# stm32f103cb_lcd32.net
KiCad netlist of a schematic drawn in EAGLE
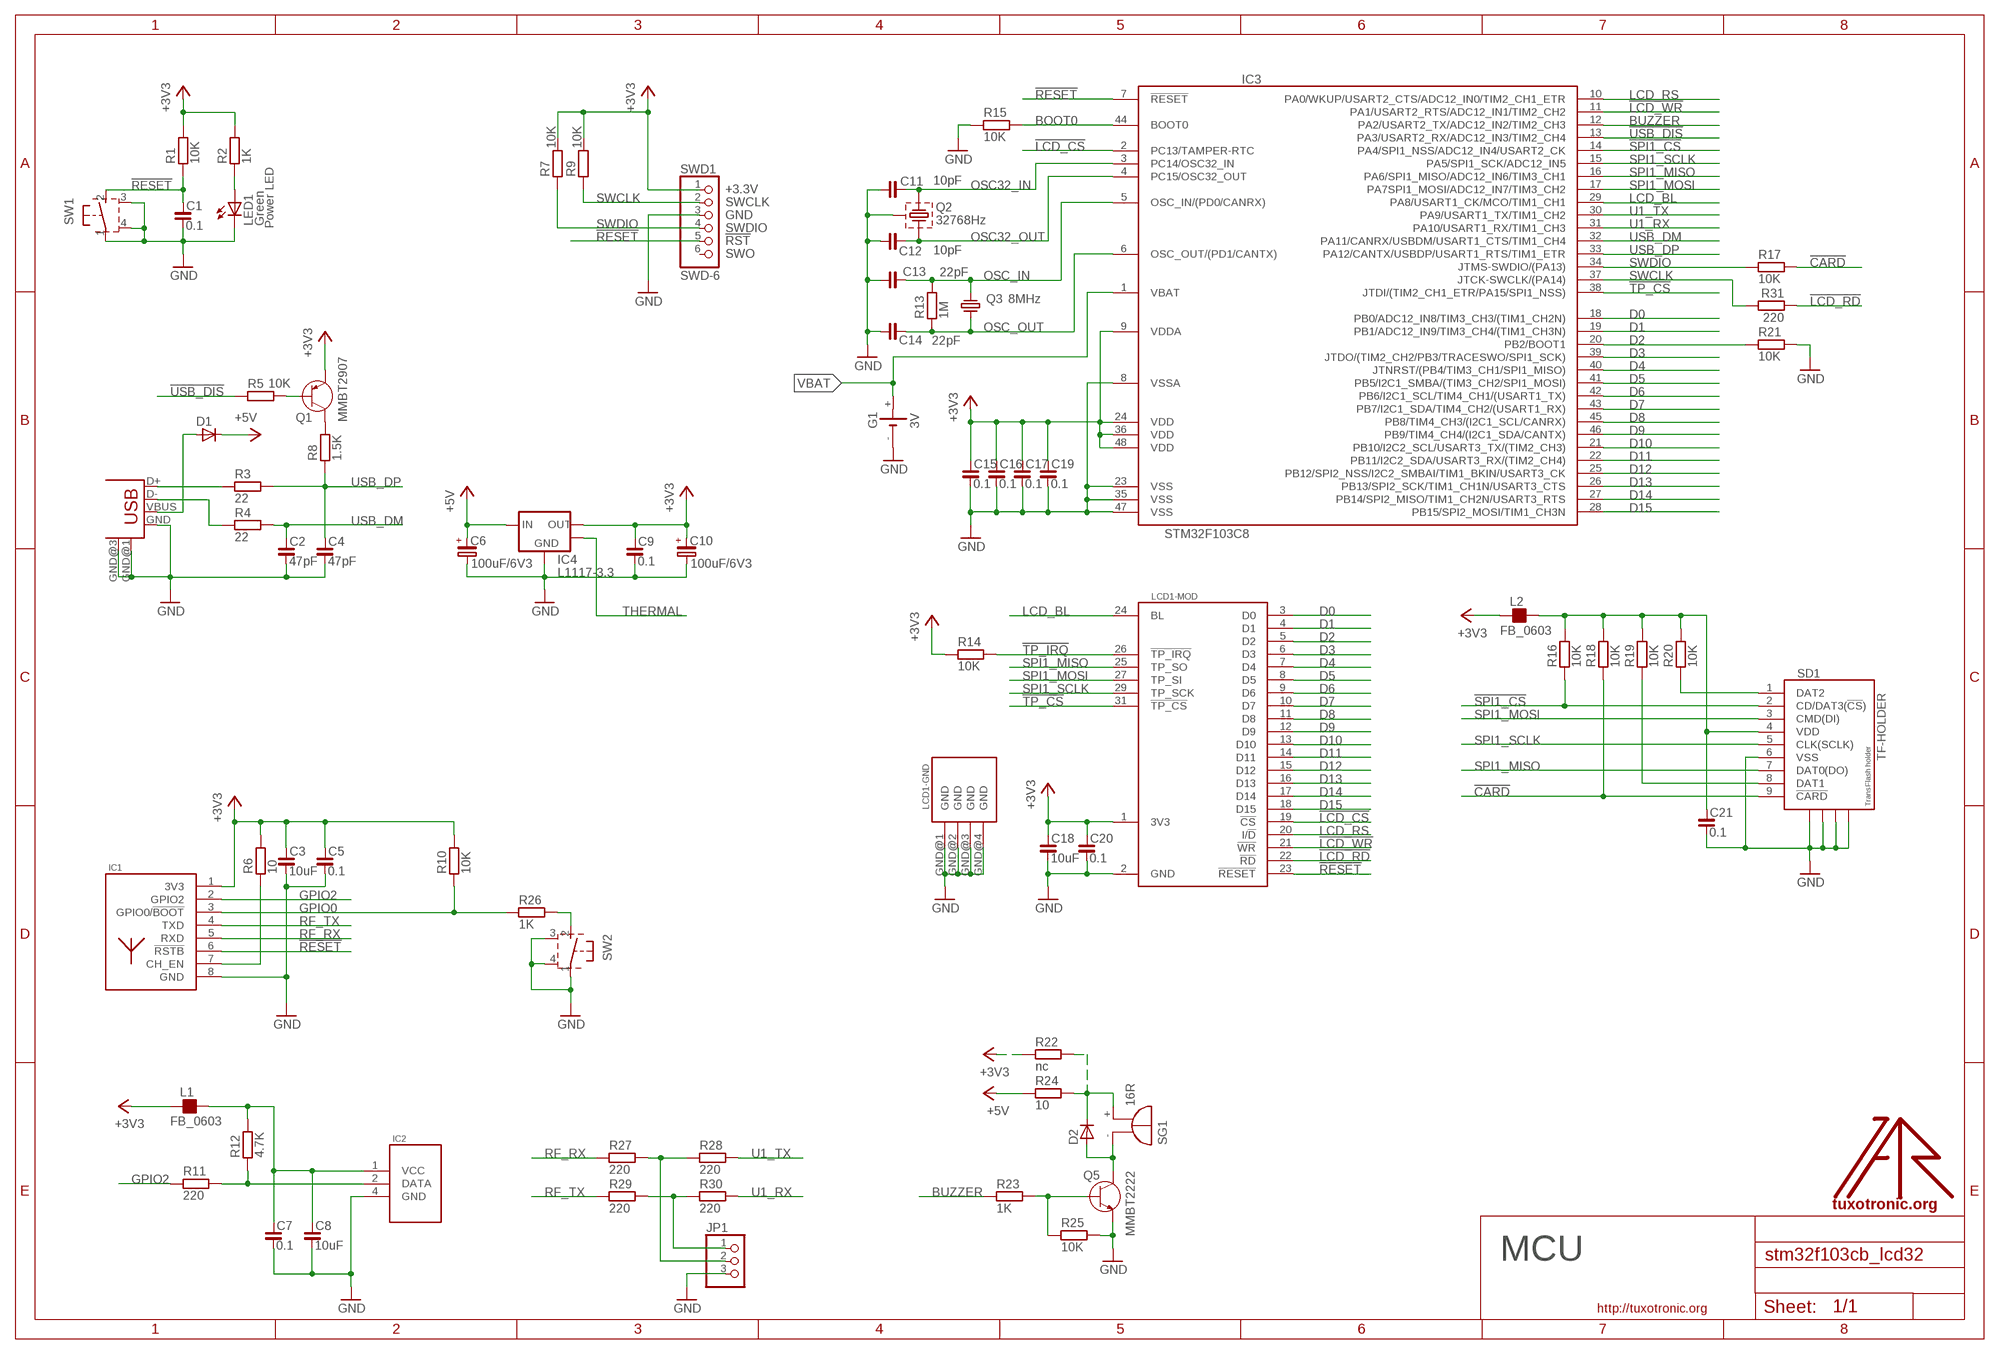
[diagram p0: schematic, sheet 1]

(export (version "E")
  (design (tool "Eeschema 10.0.6"))
  (components
    (comp (ref "C1")
      (value "0.1")
      (footprint "eagle-import:C0603")
      (libsource (lib "eagle-import") (part "C_0603"))
    )
    (comp (ref "C2")
      (value "47pF")
      (footprint "eagle-import:C0603")
      (libsource (lib "eagle-import") (part "C_0603"))
    )
    (comp (ref "C3")
      (value "10uF")
      (footprint "eagle-import:C0805")
      (libsource (lib "eagle-import") (part "C_0805"))
    )
    (comp (ref "C4")
      (value "47pF")
      (footprint "eagle-import:C0603")
      (libsource (lib "eagle-import") (part "C_0603"))
    )
    (comp (ref "C5")
      (value "0.1")
      (footprint "eagle-import:C0603")
      (libsource (lib "eagle-import") (part "C_0603"))
    )
    (comp (ref "C6")
      (value "100uF/6V3")
      (footprint "eagle-import:SMC_D")
      (libsource (lib "eagle-import") (part "CP_SMCD"))
    )
    (comp (ref "C7")
      (value "0.1")
      (footprint "eagle-import:C0603")
      (libsource (lib "eagle-import") (part "C_0603"))
    )
    (comp (ref "C8")
      (value "10uF")
      (footprint "eagle-import:C0805")
      (libsource (lib "eagle-import") (part "C_0805"))
    )
    (comp (ref "C9")
      (value "0.1")
      (footprint "eagle-import:C0805")
      (libsource (lib "eagle-import") (part "C_0805"))
    )
    (comp (ref "C10")
      (value "100uF/6V3")
      (footprint "eagle-import:SMC_D")
      (libsource (lib "eagle-import") (part "CP_SMCD"))
    )
    (comp (ref "C11")
      (value "10pF")
      (footprint "eagle-import:C0603")
      (libsource (lib "eagle-import") (part "C_0603"))
    )
    (comp (ref "C12")
      (value "10pF")
      (footprint "eagle-import:C0603")
      (libsource (lib "eagle-import") (part "C_0603"))
    )
    (comp (ref "C13")
      (value "22pF")
      (footprint "eagle-import:C0603")
      (libsource (lib "eagle-import") (part "C_0603"))
    )
    (comp (ref "C14")
      (value "22pF")
      (footprint "eagle-import:C0603")
      (libsource (lib "eagle-import") (part "C_0603"))
    )
    (comp (ref "C15")
      (value "0.1")
      (footprint "eagle-import:C0603")
      (libsource (lib "eagle-import") (part "C_0603"))
    )
    (comp (ref "C16")
      (value "0.1")
      (footprint "eagle-import:C0603")
      (libsource (lib "eagle-import") (part "C_0603"))
    )
    (comp (ref "C17")
      (value "0.1")
      (footprint "eagle-import:C0603")
      (libsource (lib "eagle-import") (part "C_0603"))
    )
    (comp (ref "C18")
      (value "10uF")
      (footprint "eagle-import:C0805")
      (libsource (lib "eagle-import") (part "C_0805"))
    )
    (comp (ref "C19")
      (value "0.1")
      (footprint "eagle-import:C0603")
      (libsource (lib "eagle-import") (part "C_0603"))
    )
    (comp (ref "C20")
      (value "0.1")
      (footprint "eagle-import:C0603")
      (libsource (lib "eagle-import") (part "C_0603"))
    )
    (comp (ref "C21")
      (value "0.1")
      (footprint "eagle-import:C0603")
      (libsource (lib "eagle-import") (part "C_0603"))
    )
    (comp (ref "D1")
      (value "D-SMB")
      (footprint "eagle-import:SMB")
      (libsource (lib "eagle-import") (part "D-SMB"))
    )
    (comp (ref "D2")
      (value "D-SOD-80")
      (footprint "eagle-import:SOD80")
      (libsource (lib "eagle-import") (part "D-SOD-80"))
    )
    (comp (ref "G1")
      (value "3V")
      (footprint "eagle-import:SMT1220")
      (libsource (lib "eagle-import") (part "1220SMT"))
    )
    (comp (ref "IC1")
      (value "ESP-11")
      (footprint "eagle-import:ESP11")
      (libsource (lib "eagle-import") (part "ESP-11"))
    )
    (comp (ref "IC2")
      (value "DHT22")
      (footprint "eagle-import:DHT")
      (libsource (lib "eagle-import") (part "DHT22"))
    )
    (comp (ref "IC3")
      (value "STM32F103C8")
      (footprint "eagle-import:LQFP48")
      (libsource (lib "eagle-import") (part "STM32F103C8"))
    )
    (comp (ref "IC4")
      (value "L1117-3.3")
      (footprint "eagle-import:SOT223-THP")
      (libsource (lib "eagle-import") (part "LM1117-THP"))
    )
    (comp (ref "JP1")
      (value "PINHD-1X3_2.54S")
      (footprint "eagle-import:1X03SMALL")
      (libsource (lib "eagle-import") (part "PINHD-1X3_2.54S"))
    )
    (comp (ref "L1")
      (value "FB_0603")
      (footprint "eagle-import:L0603")
      (libsource (lib "eagle-import") (part "FB_0603"))
    )
    (comp (ref "L2")
      (value "FB_0603")
      (footprint "eagle-import:L0603")
      (libsource (lib "eagle-import") (part "FB_0603"))
    )
    (comp (ref "LCD1")
      (value "YX32B")
      (footprint "eagle-import:YX32B")
      (libsource (lib "eagle-import") (part "YX32B"))
    )
    (comp (ref "LED1")
      (value "Green")
      (footprint "eagle-import:CHIP-LED0805")
      (libsource (lib "eagle-import") (part "LEDCHIP-LED0805"))
    )
    (comp (ref "LOGO1")
      (value "LOGO")
      (footprint "eagle-import:TT_LOGO")
      (libsource (lib "eagle-import") (part "LOGO"))
    )
    (comp (ref "Q1")
      (value "MMBT2907")
      (footprint "eagle-import:SOT23")
      (libsource (lib "eagle-import") (part "PNP-SOT23"))
    )
    (comp (ref "Q2")
      (value "32768Hz")
      (footprint "eagle-import:TC38H-G")
      (libsource (lib "eagle-import") (part "CRSTL3-"))
    )
    (comp (ref "Q3")
      (value "8MHz")
      (footprint "eagle-import:HC49_S")
      (libsource (lib "eagle-import") (part "CRYSTAL-HC49S"))
    )
    (comp (ref "Q5")
      (value "MMBT2222")
      (footprint "eagle-import:SOT23")
      (libsource (lib "eagle-import") (part "MMBT2222"))
    )
    (comp (ref "R1")
      (value "10K")
      (footprint "eagle-import:R0603")
      (libsource (lib "eagle-import") (part "R_0603"))
    )
    (comp (ref "R2")
      (value "1K")
      (footprint "eagle-import:R0603")
      (libsource (lib "eagle-import") (part "R_0603"))
    )
    (comp (ref "R3")
      (value "22")
      (footprint "eagle-import:R0603")
      (libsource (lib "eagle-import") (part "R_0603"))
    )
    (comp (ref "R4")
      (value "22")
      (footprint "eagle-import:R0603")
      (libsource (lib "eagle-import") (part "R_0603"))
    )
    (comp (ref "R5")
      (value "10K")
      (footprint "eagle-import:R0603")
      (libsource (lib "eagle-import") (part "R_0603"))
    )
    (comp (ref "R6")
      (value "10")
      (footprint "eagle-import:R0603")
      (libsource (lib "eagle-import") (part "R_0603"))
    )
    (comp (ref "R7")
      (value "10K")
      (footprint "eagle-import:R0603")
      (libsource (lib "eagle-import") (part "R_0603"))
    )
    (comp (ref "R8")
      (value "1.5K")
      (footprint "eagle-import:R0603")
      (libsource (lib "eagle-import") (part "R_0603"))
    )
    (comp (ref "R9")
      (value "10K")
      (footprint "eagle-import:R0603")
      (libsource (lib "eagle-import") (part "R_0603"))
    )
    (comp (ref "R10")
      (value "10K")
      (footprint "eagle-import:R0603")
      (libsource (lib "eagle-import") (part "R_0603"))
    )
    (comp (ref "R11")
      (value "220")
      (footprint "eagle-import:R0603")
      (libsource (lib "eagle-import") (part "R_0603"))
    )
    (comp (ref "R12")
      (value "4.7K")
      (footprint "eagle-import:R0603")
      (libsource (lib "eagle-import") (part "R_0603"))
    )
    (comp (ref "R13")
      (value "1M")
      (footprint "eagle-import:R0603")
      (libsource (lib "eagle-import") (part "R_0603"))
    )
    (comp (ref "R14")
      (value "10K")
      (footprint "eagle-import:R0603")
      (libsource (lib "eagle-import") (part "R_0603"))
    )
    (comp (ref "R15")
      (value "10K")
      (footprint "eagle-import:R0603")
      (libsource (lib "eagle-import") (part "R_0603"))
    )
    (comp (ref "R16")
      (value "10K")
      (footprint "eagle-import:R0603")
      (libsource (lib "eagle-import") (part "R_0603"))
    )
    (comp (ref "R17")
      (value "10K")
      (footprint "eagle-import:R0603")
      (libsource (lib "eagle-import") (part "R_0603"))
    )
    (comp (ref "R18")
      (value "10K")
      (footprint "eagle-import:R0603")
      (libsource (lib "eagle-import") (part "R_0603"))
    )
    (comp (ref "R19")
      (value "10K")
      (footprint "eagle-import:R0603")
      (libsource (lib "eagle-import") (part "R_0603"))
    )
    (comp (ref "R20")
      (value "10K")
      (footprint "eagle-import:R0603")
      (libsource (lib "eagle-import") (part "R_0603"))
    )
    (comp (ref "R21")
      (value "10K")
      (footprint "eagle-import:R0603")
      (libsource (lib "eagle-import") (part "R_0603"))
    )
    (comp (ref "R22")
      (value "nc")
      (footprint "eagle-import:R0603")
      (libsource (lib "eagle-import") (part "R_0603"))
    )
    (comp (ref "R23")
      (value "1K")
      (footprint "eagle-import:R0603")
      (libsource (lib "eagle-import") (part "R_0603"))
    )
    (comp (ref "R24")
      (value "10")
      (footprint "eagle-import:R0603")
      (libsource (lib "eagle-import") (part "R_0603"))
    )
    (comp (ref "R25")
      (value "10K")
      (footprint "eagle-import:R0603")
      (libsource (lib "eagle-import") (part "R_0603"))
    )
    (comp (ref "R26")
      (value "1K")
      (footprint "eagle-import:R0603")
      (libsource (lib "eagle-import") (part "R_0603"))
    )
    (comp (ref "R27")
      (value "220")
      (footprint "eagle-import:R0603")
      (libsource (lib "eagle-import") (part "R_0603"))
    )
    (comp (ref "R28")
      (value "220")
      (footprint "eagle-import:R0603")
      (libsource (lib "eagle-import") (part "R_0603"))
    )
    (comp (ref "R29")
      (value "220")
      (footprint "eagle-import:R0603")
      (libsource (lib "eagle-import") (part "R_0603"))
    )
    (comp (ref "R30")
      (value "220")
      (footprint "eagle-import:R0603")
      (libsource (lib "eagle-import") (part "R_0603"))
    )
    (comp (ref "R31")
      (value "220")
      (footprint "eagle-import:R0603")
      (libsource (lib "eagle-import") (part "R_0603"))
    )
    (comp (ref "SD1")
      (value "TF-HOLDER")
      (footprint "eagle-import:TF-PULL")
      (libsource (lib "eagle-import") (part "TF-HOLDER"))
    )
    (comp (ref "SG1")
      (value "16R")
      (footprint "eagle-import:F_QMBIII")
      (libsource (lib "eagle-import") (part "F/QMBIII"))
    )
    (comp (ref "SW1")
      (value "31-XX")
      (footprint "eagle-import:B3F-31XX")
      (libsource (lib "eagle-import") (part "31-XX"))
    )
    (comp (ref "SW2")
      (value "31-XX")
      (footprint "eagle-import:B3F-31XX")
      (libsource (lib "eagle-import") (part "31-XX"))
    )
    (comp (ref "SWD1")
      (value "SWD-6")
      (footprint "eagle-import:JTAG6PIN")
      (libsource (lib "eagle-import") (part "SWD-6"))
    )
    (comp (ref "USB1")
      (value "USB-MB-S")
      (footprint "eagle-import:USB-MB-S")
      (libsource (lib "eagle-import") (part "USB-MB-S"))
    )
  )
  (nets
    (net (code "1") (name "+3V3") (class "Default")
      (node (ref "C10") (pin "+") (pinfunction "+_+") (pintype "passive"))
      (node (ref "C15") (pin "1") (pinfunction "1_1") (pintype "passive"))
      (node (ref "C16") (pin "1") (pinfunction "1_1") (pintype "passive"))
      (node (ref "C17") (pin "1") (pinfunction "1_1") (pintype "passive"))
      (node (ref "C18") (pin "1") (pinfunction "1_1") (pintype "passive"))
      (node (ref "C19") (pin "1") (pinfunction "1_1") (pintype "passive"))
      (node (ref "C20") (pin "1") (pinfunction "1_1") (pintype "passive"))
      (node (ref "C3") (pin "1") (pinfunction "1_1") (pintype "passive"))
      (node (ref "C5") (pin "1") (pinfunction "1_1") (pintype "passive"))
      (node (ref "C9") (pin "1") (pinfunction "1_1") (pintype "passive"))
      (node (ref "IC1") (pin "1") (pinfunction "3V3_1") (pintype "power_in"))
      (node (ref "IC3") (pin "24") (pinfunction "VDD_24") (pintype "power_in"))
      (node (ref "IC3") (pin "36") (pinfunction "VDD_36") (pintype "power_in"))
      (node (ref "IC3") (pin "48") (pinfunction "VDD_48") (pintype "power_in"))
      (node (ref "IC3") (pin "9") (pinfunction "VDDA_9") (pintype "power_in"))
      (node (ref "IC4") (pin "2") (pinfunction "OUT_2") (pintype "power_in"))
      (node (ref "L1") (pin "1") (pinfunction "1_1") (pintype "passive"))
      (node (ref "L2") (pin "1") (pinfunction "1_1") (pintype "passive"))
      (node (ref "LCD1") (pin "1") (pinfunction "3V3_1") (pintype "power_in"))
      (node (ref "Q1") (pin "2") (pinfunction "E_2") (pintype "passive"))
      (node (ref "R1") (pin "2") (pinfunction "2_2") (pintype "passive"))
      (node (ref "R10") (pin "2") (pinfunction "2_2") (pintype "passive"))
      (node (ref "R14") (pin "1") (pinfunction "1_1") (pintype "passive"))
      (node (ref "R2") (pin "2") (pinfunction "2_2") (pintype "passive"))
      (node (ref "R22") (pin "1") (pinfunction "1_1") (pintype "passive"))
      (node (ref "R6") (pin "2") (pinfunction "2_2") (pintype "passive"))
      (node (ref "R7") (pin "2") (pinfunction "2_2") (pintype "passive"))
      (node (ref "R9") (pin "2") (pinfunction "2_2") (pintype "passive"))
      (node (ref "SWD1") (pin "1") (pinfunction "1_1") (pintype "passive"))
    )
    (net (code "2") (name "+5V") (class "Default")
      (node (ref "C6") (pin "+") (pinfunction "+_+") (pintype "passive"))
      (node (ref "D1") (pin "1") (pinfunction "C_1") (pintype "passive"))
      (node (ref "IC4") (pin "3") (pinfunction "IN_3") (pintype "power_in"))
      (node (ref "R24") (pin "1") (pinfunction "1_1") (pintype "passive"))
    )
    (net (code "3") (name "/BOOT0") (class "Default")
      (node (ref "IC3") (pin "44") (pinfunction "BOOT0_44") (pintype "input"))
      (node (ref "R15") (pin "2") (pinfunction "2_2") (pintype "passive"))
    )
    (net (code "4") (name "/BUZZER") (class "Default")
      (node (ref "IC3") (pin "12") (pinfunction "PA2/USART2_TX/ADC12_IN2/TIM2_CH3_12") (pintype "bidirectional"))
      (node (ref "R23") (pin "1") (pinfunction "1_1") (pintype "passive"))
    )
    (net (code "5") (name "/D0") (class "Default")
      (node (ref "IC3") (pin "18") (pinfunction "PB0/ADC12_IN8/TIM3_CH3/(TIM1_CH2N)_18") (pintype "bidirectional"))
      (node (ref "LCD1") (pin "3") (pinfunction "D0_3") (pintype "bidirectional"))
    )
    (net (code "6") (name "/D1") (class "Default")
      (node (ref "IC3") (pin "19") (pinfunction "PB1/ADC12_IN9/TIM3_CH4/(TIM1_CH3N)_19") (pintype "bidirectional"))
      (node (ref "LCD1") (pin "4") (pinfunction "D1_4") (pintype "bidirectional"))
    )
    (net (code "7") (name "/D2") (class "Default")
      (node (ref "IC3") (pin "20") (pinfunction "PB2/BOOT1_20") (pintype "bidirectional"))
      (node (ref "LCD1") (pin "5") (pinfunction "D2_5") (pintype "bidirectional"))
      (node (ref "R21") (pin "1") (pinfunction "1_1") (pintype "passive"))
    )
    (net (code "8") (name "/D3") (class "Default")
      (node (ref "IC3") (pin "39") (pinfunction "JTDO/(TIM2_CH2/PB3/TRACESWO/SPI1_SCK)_39") (pintype "bidirectional"))
      (node (ref "LCD1") (pin "6") (pinfunction "D3_6") (pintype "bidirectional"))
    )
    (net (code "9") (name "/D4") (class "Default")
      (node (ref "IC3") (pin "40") (pinfunction "JTNRST/(PB4/TIM3_CH1/SPI1_MISO)_40") (pintype "bidirectional"))
      (node (ref "LCD1") (pin "7") (pinfunction "D4_7") (pintype "bidirectional"))
    )
    (net (code "10") (name "/D5") (class "Default")
      (node (ref "IC3") (pin "41") (pinfunction "PB5/I2C1_SMBA/(TIM3_CH2/SPI1_MOSI)_41") (pintype "bidirectional"))
      (node (ref "LCD1") (pin "8") (pinfunction "D5_8") (pintype "bidirectional"))
    )
    (net (code "11") (name "/D6") (class "Default")
      (node (ref "IC3") (pin "42") (pinfunction "PB6/I2C1_SCL/TIM4_CH1/(USART1_TX)_42") (pintype "bidirectional"))
      (node (ref "LCD1") (pin "9") (pinfunction "D6_9") (pintype "bidirectional"))
    )
    (net (code "12") (name "/D7") (class "Default")
      (node (ref "IC3") (pin "43") (pinfunction "PB7/I2C1_SDA/TIM4_CH2/(USART1_RX)_43") (pintype "bidirectional"))
      (node (ref "LCD1") (pin "10") (pinfunction "D7_10") (pintype "bidirectional"))
    )
    (net (code "13") (name "/D8") (class "Default")
      (node (ref "IC3") (pin "45") (pinfunction "PB8/TIM4_CH3/(I2C1_SCL/CANRX)_45") (pintype "bidirectional"))
      (node (ref "LCD1") (pin "11") (pinfunction "D8_11") (pintype "bidirectional"))
    )
    (net (code "14") (name "/D9") (class "Default")
      (node (ref "IC3") (pin "46") (pinfunction "PB9/TIM4_CH4/(I2C1_SDA/CANTX)_46") (pintype "bidirectional"))
      (node (ref "LCD1") (pin "12") (pinfunction "D9_12") (pintype "bidirectional"))
    )
    (net (code "15") (name "/D10") (class "Default")
      (node (ref "IC3") (pin "21") (pinfunction "PB10/I2C2_SCL/USART3_TX/(TIM2_CH3)_21") (pintype "bidirectional"))
      (node (ref "LCD1") (pin "13") (pinfunction "D10_13") (pintype "bidirectional"))
    )
    (net (code "16") (name "/D11") (class "Default")
      (node (ref "IC3") (pin "22") (pinfunction "PB11/I2C2_SDA/USART3_RX/(TIM2_CH4)_22") (pintype "bidirectional"))
      (node (ref "LCD1") (pin "14") (pinfunction "D11_14") (pintype "bidirectional"))
    )
    (net (code "17") (name "/D12") (class "Default")
      (node (ref "IC3") (pin "25") (pinfunction "PB12/SPI2_NSS/I2C2_SMBAI/TIM1_BKIN/USART3_CK_25") (pintype "bidirectional"))
      (node (ref "LCD1") (pin "15") (pinfunction "D12_15") (pintype "bidirectional"))
    )
    (net (code "18") (name "/D13") (class "Default")
      (node (ref "IC3") (pin "26") (pinfunction "PB13/SPI2_SCK/TIM1_CH1N/USART3_CTS_26") (pintype "bidirectional"))
      (node (ref "LCD1") (pin "16") (pinfunction "D13_16") (pintype "bidirectional"))
    )
    (net (code "19") (name "/D14") (class "Default")
      (node (ref "IC3") (pin "27") (pinfunction "PB14/SPI2_MISO/TIM1_CH2N/USART3_RTS_27") (pintype "bidirectional"))
      (node (ref "LCD1") (pin "17") (pinfunction "D14_17") (pintype "bidirectional"))
    )
    (net (code "20") (name "/D15") (class "Default")
      (node (ref "IC3") (pin "28") (pinfunction "PB15/SPI2_MOSI/TIM1_CH3N_28") (pintype "bidirectional"))
      (node (ref "LCD1") (pin "18") (pinfunction "D15_18") (pintype "bidirectional"))
    )
    (net (code "21") (name "/GPIO0") (class "Default")
      (node (ref "IC1") (pin "3") (pinfunction "GPIO0/~{BOOT}_3") (pintype "bidirectional"))
      (node (ref "R10") (pin "1") (pinfunction "1_1") (pintype "passive"))
      (node (ref "R26") (pin "1") (pinfunction "1_1") (pintype "passive"))
    )
    (net (code "22") (name "/GPIO2") (class "Default")
      (node (ref "IC1") (pin "2") (pinfunction "GPIO2_2") (pintype "bidirectional"))
      (node (ref "R11") (pin "1") (pinfunction "1_1") (pintype "passive"))
    )
    (net (code "23") (name "/LCD_BL") (class "Default")
      (node (ref "IC3") (pin "29") (pinfunction "PA8/USART1_CK/MCO/TIM1_CH1_29") (pintype "bidirectional"))
      (node (ref "LCD1") (pin "24") (pinfunction "BL_24") (pintype "input"))
    )
    (net (code "24") (name "/LCD_RS") (class "Default")
      (node (ref "IC3") (pin "10") (pinfunction "PA0/WKUP/USART2_CTS/ADC12_IN0/TIM2_CH1_ETR_10") (pintype "bidirectional"))
      (node (ref "LCD1") (pin "20") (pinfunction "I/~{D}_20") (pintype "input"))
    )
    (net (code "25") (name "/OSC32_IN") (class "Default")
      (node (ref "C11") (pin "1") (pinfunction "1_1") (pintype "passive"))
      (node (ref "IC3") (pin "3") (pinfunction "PC14/OSC32_IN_3") (pintype "bidirectional"))
      (node (ref "Q2") (pin "2") (pinfunction "2_2") (pintype "passive"))
    )
    (net (code "26") (name "/OSC32_OUT") (class "Default")
      (node (ref "C12") (pin "1") (pinfunction "1_1") (pintype "passive"))
      (node (ref "IC3") (pin "4") (pinfunction "PC15/OSC32_OUT_4") (pintype "bidirectional"))
      (node (ref "Q2") (pin "1") (pinfunction "1_1") (pintype "passive"))
    )
    (net (code "27") (name "/OSC_IN") (class "Default")
      (node (ref "C13") (pin "1") (pinfunction "1_1") (pintype "passive"))
      (node (ref "IC3") (pin "5") (pinfunction "OSC_IN/(PD0/CANRX)_5") (pintype "input"))
      (node (ref "Q3") (pin "1") (pinfunction "1_1") (pintype "passive"))
      (node (ref "R13") (pin "2") (pinfunction "2_2") (pintype "passive"))
    )
    (net (code "28") (name "/OSC_OUT") (class "Default")
      (node (ref "C14") (pin "1") (pinfunction "1_1") (pintype "passive"))
      (node (ref "IC3") (pin "6") (pinfunction "OSC_OUT/(PD1/CANTX)_6") (pintype "output"))
      (node (ref "Q3") (pin "2") (pinfunction "2_2") (pintype "passive"))
      (node (ref "R13") (pin "1") (pinfunction "1_1") (pintype "passive"))
    )
    (net (code "29") (name "/RF_RX") (class "Default")
      (node (ref "IC1") (pin "5") (pinfunction "RXD_5") (pintype "input"))
      (node (ref "R27") (pin "1") (pinfunction "1_1") (pintype "passive"))
    )
    (net (code "30") (name "/RF_TX") (class "Default")
      (node (ref "IC1") (pin "4") (pinfunction "TXD_4") (pintype "output"))
      (node (ref "R29") (pin "1") (pinfunction "1_1") (pintype "passive"))
    )
    (net (code "31") (name "/SPI1_MISO") (class "Default")
      (node (ref "IC3") (pin "16") (pinfunction "PA6/SPI1_MISO/ADC12_IN6/TIM3_CH1_16") (pintype "bidirectional"))
      (node (ref "LCD1") (pin "25") (pinfunction "TP_SO_25") (pintype "output"))
      (node (ref "SD1") (pin "7") (pinfunction "DAT0(DO)_7") (pintype "bidirectional"))
    )
    (net (code "32") (name "/SPI1_MOSI") (class "Default")
      (node (ref "IC3") (pin "17") (pinfunction "PA7SPI1_MOSI/ADC12_IN7/TIM3_CH2_17") (pintype "bidirectional"))
      (node (ref "LCD1") (pin "27") (pinfunction "TP_SI_27") (pintype "input"))
      (node (ref "SD1") (pin "3") (pinfunction "CMD(DI)_3") (pintype "bidirectional"))
    )
    (net (code "33") (name "/SPI1_SCLK") (class "Default")
      (node (ref "IC3") (pin "15") (pinfunction "PA5/SPI1_SCK/ADC12_IN5_15") (pintype "bidirectional"))
      (node (ref "LCD1") (pin "29") (pinfunction "TP_SCK_29") (pintype "input"))
      (node (ref "SD1") (pin "5") (pinfunction "CLK(SCLK)_5") (pintype "input"))
    )
    (net (code "34") (name "/SWCLK") (class "Default")
      (node (ref "IC3") (pin "37") (pinfunction "JTCK-SWCLK/(PA14)_37") (pintype "bidirectional"))
      (node (ref "R31") (pin "2") (pinfunction "2_2") (pintype "passive"))
      (node (ref "R9") (pin "1") (pinfunction "1_1") (pintype "passive"))
      (node (ref "SWD1") (pin "2") (pinfunction "2_2") (pintype "passive"))
    )
    (net (code "35") (name "/SWDIO") (class "Default")
      (node (ref "IC3") (pin "34") (pinfunction "JTMS-SWDIO/(PA13)_34") (pintype "bidirectional"))
      (node (ref "R17") (pin "1") (pinfunction "1_1") (pintype "passive"))
      (node (ref "R7") (pin "1") (pinfunction "1_1") (pintype "passive"))
      (node (ref "SWD1") (pin "4") (pinfunction "4_4") (pintype "passive"))
    )
    (net (code "36") (name "/THERMAL") (class "Default")
      (node (ref "IC4") (pin "4") (pinfunction "MASS_4") (pintype "passive"))
    )
    (net (code "37") (name "/U1_RX") (class "Default")
      (node (ref "IC3") (pin "31") (pinfunction "PA10/USART1_RX/TIM1_CH3_31") (pintype "bidirectional"))
      (node (ref "R30") (pin "2") (pinfunction "2_2") (pintype "passive"))
    )
    (net (code "38") (name "/U1_TX") (class "Default")
      (node (ref "IC3") (pin "30") (pinfunction "PA9/USART1_TX/TIM1_CH2_30") (pintype "bidirectional"))
      (node (ref "R28") (pin "2") (pinfunction "2_2") (pintype "passive"))
    )
    (net (code "39") (name "/USB_DM") (class "Default")
      (node (ref "C2") (pin "1") (pinfunction "1_1") (pintype "passive"))
      (node (ref "IC3") (pin "32") (pinfunction "PA11/CANRX/USBDM/USART1_CTS/TIM1_CH4_32") (pintype "bidirectional"))
      (node (ref "R4") (pin "2") (pinfunction "2_2") (pintype "passive"))
    )
    (net (code "40") (name "/USB_DP") (class "Default")
      (node (ref "C4") (pin "1") (pinfunction "1_1") (pintype "passive"))
      (node (ref "IC3") (pin "33") (pinfunction "PA12/CANTX/USBDP/USART1_RTS/TIM1_ETR_33") (pintype "bidirectional"))
      (node (ref "R3") (pin "2") (pinfunction "2_2") (pintype "passive"))
      (node (ref "R8") (pin "1") (pinfunction "1_1") (pintype "passive"))
    )
    (net (code "41") (name "/~{CARD}") (class "Default")
      (node (ref "R17") (pin "2") (pinfunction "2_2") (pintype "passive"))
      (node (ref "R18") (pin "1") (pinfunction "1_1") (pintype "passive"))
      (node (ref "SD1") (pin "9") (pinfunction "~{CARD}_9") (pintype "passive"))
    )
    (net (code "42") (name "/~{LCD_CS}") (class "Default")
      (node (ref "IC3") (pin "2") (pinfunction "PC13/TAMPER-RTC_2") (pintype "bidirectional"))
      (node (ref "LCD1") (pin "19") (pinfunction "~{CS}_19") (pintype "input"))
    )
    (net (code "43") (name "/~{LCD_RD}") (class "Default")
      (node (ref "LCD1") (pin "22") (pinfunction "~{RD}_22") (pintype "input"))
      (node (ref "R31") (pin "1") (pinfunction "1_1") (pintype "passive"))
    )
    (net (code "44") (name "/~{LCD_WR}") (class "Default")
      (node (ref "IC3") (pin "11") (pinfunction "PA1/USART2_RTS/ADC12_IN1/TIM2_CH2_11") (pintype "bidirectional"))
      (node (ref "LCD1") (pin "21") (pinfunction "~{WR}_21") (pintype "input"))
    )
    (net (code "45") (name "/~{RESET}") (class "Default")
      (node (ref "C1") (pin "1") (pinfunction "1_1") (pintype "passive"))
      (node (ref "IC1") (pin "6") (pinfunction "~{RSTB}_6") (pintype "input"))
      (node (ref "IC3") (pin "7") (pinfunction "~{RESET}_7") (pintype "input"))
      (node (ref "LCD1") (pin "23") (pinfunction "~{RESET}_23") (pintype "input"))
      (node (ref "R1") (pin "1") (pinfunction "1_1") (pintype "passive"))
      (node (ref "SW1") (pin "2") (pinfunction "S_2") (pintype "passive"))
      (node (ref "SWD1") (pin "5") (pinfunction "5_5") (pintype "passive"))
    )
    (net (code "46") (name "/~{SPI1_CS}") (class "Default")
      (node (ref "IC3") (pin "14") (pinfunction "PA4/SPI1_NSS/ADC12_IN4/USART2_CK_14") (pintype "bidirectional"))
      (node (ref "R16") (pin "1") (pinfunction "1_1") (pintype "passive"))
      (node (ref "SD1") (pin "2") (pinfunction "CD/DAT3(~{CS})_2") (pintype "bidirectional"))
    )
    (net (code "47") (name "/~{TP_CS}") (class "Default")
      (node (ref "IC3") (pin "38") (pinfunction "JTDI/(TIM2_CH1_ETR/PA15/SPI1_NSS)_38") (pintype "bidirectional"))
      (node (ref "LCD1") (pin "31") (pinfunction "~{TP_CS}_31") (pintype "input"))
    )
    (net (code "48") (name "/~{TP_IRQ}") (class "Default")
      (node (ref "LCD1") (pin "26") (pinfunction "~{TP_IRQ}_26") (pintype "output"))
      (node (ref "R14") (pin "2") (pinfunction "2_2") (pintype "passive"))
    )
    (net (code "49") (name "/~{USB_DIS}") (class "Default")
      (node (ref "IC3") (pin "13") (pinfunction "PA3/USART2_RX/ADC12_IN3/TIM2_CH4_13") (pintype "bidirectional"))
      (node (ref "R5") (pin "1") (pinfunction "1_1") (pintype "passive"))
    )
    (net (code "50") (name "GND") (class "Default")
      (node (ref "C1") (pin "2") (pinfunction "2_2") (pintype "passive"))
      (node (ref "C10") (pin "-") (pinfunction "-_-") (pintype "passive"))
      (node (ref "C11") (pin "2") (pinfunction "2_2") (pintype "passive"))
      (node (ref "C12") (pin "2") (pinfunction "2_2") (pintype "passive"))
      (node (ref "C13") (pin "2") (pinfunction "2_2") (pintype "passive"))
      (node (ref "C14") (pin "2") (pinfunction "2_2") (pintype "passive"))
      (node (ref "C15") (pin "2") (pinfunction "2_2") (pintype "passive"))
      (node (ref "C16") (pin "2") (pinfunction "2_2") (pintype "passive"))
      (node (ref "C17") (pin "2") (pinfunction "2_2") (pintype "passive"))
      (node (ref "C18") (pin "2") (pinfunction "2_2") (pintype "passive"))
      (node (ref "C19") (pin "2") (pinfunction "2_2") (pintype "passive"))
      (node (ref "C2") (pin "2") (pinfunction "2_2") (pintype "passive"))
      (node (ref "C20") (pin "2") (pinfunction "2_2") (pintype "passive"))
      (node (ref "C21") (pin "2") (pinfunction "2_2") (pintype "passive"))
      (node (ref "C3") (pin "2") (pinfunction "2_2") (pintype "passive"))
      (node (ref "C4") (pin "2") (pinfunction "2_2") (pintype "passive"))
      (node (ref "C5") (pin "2") (pinfunction "2_2") (pintype "passive"))
      (node (ref "C6") (pin "-") (pinfunction "-_-") (pintype "passive"))
      (node (ref "C7") (pin "2") (pinfunction "2_2") (pintype "passive"))
      (node (ref "C8") (pin "2") (pinfunction "2_2") (pintype "passive"))
      (node (ref "C9") (pin "2") (pinfunction "2_2") (pintype "passive"))
      (node (ref "G1") (pin "-") (pinfunction "-_-") (pintype "passive"))
      (node (ref "IC1") (pin "8") (pinfunction "GND_8") (pintype "power_in"))
      (node (ref "IC2") (pin "4") (pinfunction "GND_4") (pintype "power_in"))
      (node (ref "IC3") (pin "23") (pinfunction "VSS_23") (pintype "power_in"))
      (node (ref "IC3") (pin "35") (pinfunction "VSS_35") (pintype "power_in"))
      (node (ref "IC3") (pin "47") (pinfunction "VSS_47") (pintype "power_in"))
      (node (ref "IC3") (pin "8") (pinfunction "VSSA_8") (pintype "power_in"))
      (node (ref "IC4") (pin "1") (pinfunction "GND_1") (pintype "power_in"))
      (node (ref "JP1") (pin "3") (pinfunction "3_3") (pintype "passive"))
      (node (ref "LCD1") (pin "2") (pinfunction "GND_2") (pintype "power_in"))
      (node (ref "LCD1") (pin "GND@1") (pinfunction "GND_GND@1") (pintype "power_in"))
      (node (ref "LCD1") (pin "GND@2") (pinfunction "GND_GND@2") (pintype "power_in"))
      (node (ref "LCD1") (pin "GND@3") (pinfunction "GND_GND@3") (pintype "power_in"))
      (node (ref "LCD1") (pin "GND@4") (pinfunction "GND_GND@4") (pintype "power_in"))
      (node (ref "LED1") (pin "C") (pinfunction "C_C") (pintype "passive"))
      (node (ref "Q2") (pin "GND") (pinfunction "P$1_GND") (pintype "passive"))
      (node (ref "Q5") (pin "2") (pinfunction "E_2") (pintype "passive"))
      (node (ref "R15") (pin "1") (pinfunction "1_1") (pintype "passive"))
      (node (ref "R21") (pin "2") (pinfunction "2_2") (pintype "passive"))
      (node (ref "R25") (pin "2") (pinfunction "2_2") (pintype "passive"))
      (node (ref "SD1") (pin "6") (pinfunction "VSS_6") (pintype "power_in"))
      (node (ref "SD1") (pin "S1") (pinfunction "S1_S1") (pintype "passive"))
      (node (ref "SD1") (pin "S2") (pinfunction "S2_S2") (pintype "passive"))
      (node (ref "SD1") (pin "S3") (pinfunction "S3_S3") (pintype "passive"))
      (node (ref "SD1") (pin "S4") (pinfunction "S4_S4") (pintype "passive"))
      (node (ref "SW1") (pin "1") (pinfunction "P_1") (pintype "passive"))
      (node (ref "SW1") (pin "3") (pinfunction "GND1_3") (pintype "passive"))
      (node (ref "SW1") (pin "4") (pinfunction "GND2_4") (pintype "passive"))
      (node (ref "SW2") (pin "1") (pinfunction "P_1") (pintype "passive"))
      (node (ref "SW2") (pin "3") (pinfunction "GND1_3") (pintype "passive"))
      (node (ref "SW2") (pin "4") (pinfunction "GND2_4") (pintype "passive"))
      (node (ref "SWD1") (pin "3") (pinfunction "3_3") (pintype "passive"))
      (node (ref "USB1") (pin "GND") (pinfunction "GND_GND") (pintype "bidirectional"))
      (node (ref "USB1") (pin "GND@1") (pinfunction "GND_GND@1") (pintype "bidirectional"))
      (node (ref "USB1") (pin "GND@3") (pinfunction "GND_GND@3") (pintype "bidirectional"))
    )
    (net (code "51") (name "Net-(D1-A)") (class "Default")
      (node (ref "D1") (pin "2") (pinfunction "A_2") (pintype "passive"))
      (node (ref "USB1") (pin "VBUS") (pinfunction "VBUS_VBUS") (pintype "bidirectional"))
    )
    (net (code "52") (name "Net-(D2-A)") (class "Default")
      (node (ref "D2") (pin "2") (pinfunction "A_2") (pintype "passive"))
      (node (ref "Q5") (pin "3") (pinfunction "C_3") (pintype "passive"))
      (node (ref "SG1") (pin "-") (pinfunction "+_-") (pintype "passive"))
    )
    (net (code "53") (name "Net-(D2-C)") (class "Default")
      (node (ref "D2") (pin "1") (pinfunction "C_1") (pintype "passive"))
      (node (ref "R22") (pin "2") (pinfunction "2_2") (pintype "passive"))
      (node (ref "R24") (pin "2") (pinfunction "2_2") (pintype "passive"))
      (node (ref "SG1") (pin "+") (pinfunction "-_+") (pintype "passive"))
    )
    (net (code "54") (name "Net-(IC1-CH_EN)") (class "Default")
      (node (ref "IC1") (pin "7") (pinfunction "CH_EN_7") (pintype "input"))
      (node (ref "R6") (pin "1") (pinfunction "1_1") (pintype "passive"))
    )
    (net (code "55") (name "Net-(IC2-DATA)") (class "Default")
      (node (ref "IC2") (pin "2") (pinfunction "DATA_2") (pintype "bidirectional"))
      (node (ref "R11") (pin "2") (pinfunction "2_2") (pintype "passive"))
      (node (ref "R12") (pin "1") (pinfunction "1_1") (pintype "passive"))
    )
    (net (code "56") (name "Net-(IC2-VCC)") (class "Default")
      (node (ref "C7") (pin "1") (pinfunction "1_1") (pintype "passive"))
      (node (ref "C8") (pin "1") (pinfunction "1_1") (pintype "passive"))
      (node (ref "IC2") (pin "1") (pinfunction "VCC_1") (pintype "power_in"))
      (node (ref "L1") (pin "2") (pinfunction "2_2") (pintype "passive"))
      (node (ref "R12") (pin "2") (pinfunction "2_2") (pintype "passive"))
    )
    (net (code "57") (name "Net-(JP1-Pad1)") (class "Default")
      (node (ref "JP1") (pin "1") (pinfunction "1_1") (pintype "passive"))
      (node (ref "R29") (pin "2") (pinfunction "2_2") (pintype "passive"))
      (node (ref "R30") (pin "1") (pinfunction "1_1") (pintype "passive"))
    )
    (net (code "58") (name "Net-(JP1-Pad2)") (class "Default")
      (node (ref "JP1") (pin "2") (pinfunction "2_2") (pintype "passive"))
      (node (ref "R27") (pin "2") (pinfunction "2_2") (pintype "passive"))
      (node (ref "R28") (pin "1") (pinfunction "1_1") (pintype "passive"))
    )
    (net (code "59") (name "Net-(LED1-PadA)") (class "Default")
      (node (ref "LED1") (pin "A") (pinfunction "A_A") (pintype "passive"))
      (node (ref "R2") (pin "1") (pinfunction "1_1") (pintype "passive"))
    )
    (net (code "60") (name "Net-(Q1-B)") (class "Default")
      (node (ref "Q1") (pin "1") (pinfunction "B_1") (pintype "passive"))
      (node (ref "R5") (pin "2") (pinfunction "2_2") (pintype "passive"))
    )
    (net (code "61") (name "Net-(Q1-C)") (class "Default")
      (node (ref "Q1") (pin "3") (pinfunction "C_3") (pintype "passive"))
      (node (ref "R8") (pin "2") (pinfunction "2_2") (pintype "passive"))
    )
    (net (code "62") (name "Net-(Q5-B)") (class "Default")
      (node (ref "Q5") (pin "1") (pinfunction "B_1") (pintype "passive"))
      (node (ref "R23") (pin "2") (pinfunction "2_2") (pintype "passive"))
      (node (ref "R25") (pin "1") (pinfunction "1_1") (pintype "passive"))
    )
    (net (code "63") (name "Net-(R3-Pad1)") (class "Default")
      (node (ref "R3") (pin "1") (pinfunction "1_1") (pintype "passive"))
      (node (ref "USB1") (pin "D+") (pinfunction "D+_D+") (pintype "bidirectional"))
    )
    (net (code "64") (name "Net-(R4-Pad1)") (class "Default")
      (node (ref "R4") (pin "1") (pinfunction "1_1") (pintype "passive"))
      (node (ref "USB1") (pin "D-") (pinfunction "D-_D-") (pintype "bidirectional"))
    )
    (net (code "65") (name "Net-(SD1-DAT1)") (class "Default")
      (node (ref "R19") (pin "1") (pinfunction "1_1") (pintype "passive"))
      (node (ref "SD1") (pin "8") (pinfunction "DAT1_8") (pintype "bidirectional"))
    )
    (net (code "66") (name "Net-(SD1-DAT2)") (class "Default")
      (node (ref "R20") (pin "1") (pinfunction "1_1") (pintype "passive"))
      (node (ref "SD1") (pin "1") (pinfunction "DAT2_1") (pintype "bidirectional"))
    )
    (net (code "67") (name "Net-(SD1-VDD)") (class "Default")
      (node (ref "C21") (pin "1") (pinfunction "1_1") (pintype "passive"))
      (node (ref "L2") (pin "2") (pinfunction "2_2") (pintype "passive"))
      (node (ref "R16") (pin "2") (pinfunction "2_2") (pintype "passive"))
      (node (ref "R18") (pin "2") (pinfunction "2_2") (pintype "passive"))
      (node (ref "R19") (pin "2") (pinfunction "2_2") (pintype "passive"))
      (node (ref "R20") (pin "2") (pinfunction "2_2") (pintype "passive"))
      (node (ref "SD1") (pin "4") (pinfunction "VDD_4") (pintype "power_in"))
    )
    (net (code "68") (name "Net-(SW2-S)") (class "Default")
      (node (ref "R26") (pin "2") (pinfunction "2_2") (pintype "passive"))
      (node (ref "SW2") (pin "2") (pinfunction "S_2") (pintype "passive"))
    )
    (net (code "69") (name "VBAT") (class "Default")
      (node (ref "G1") (pin "+") (pinfunction "+_+") (pintype "passive"))
      (node (ref "IC3") (pin "1") (pinfunction "VBAT_1") (pintype "power_in"))
    )
    (net (code "70") (name "unconnected-(SWD1-Pad6)") (class "Default")
      (node (ref "SWD1") (pin "6") (pinfunction "6_6") (pintype "passive"))
    )
  )
)
